# Proiect_TSC_v6.net
KiCad netlist of a schematic drawn in EAGLE
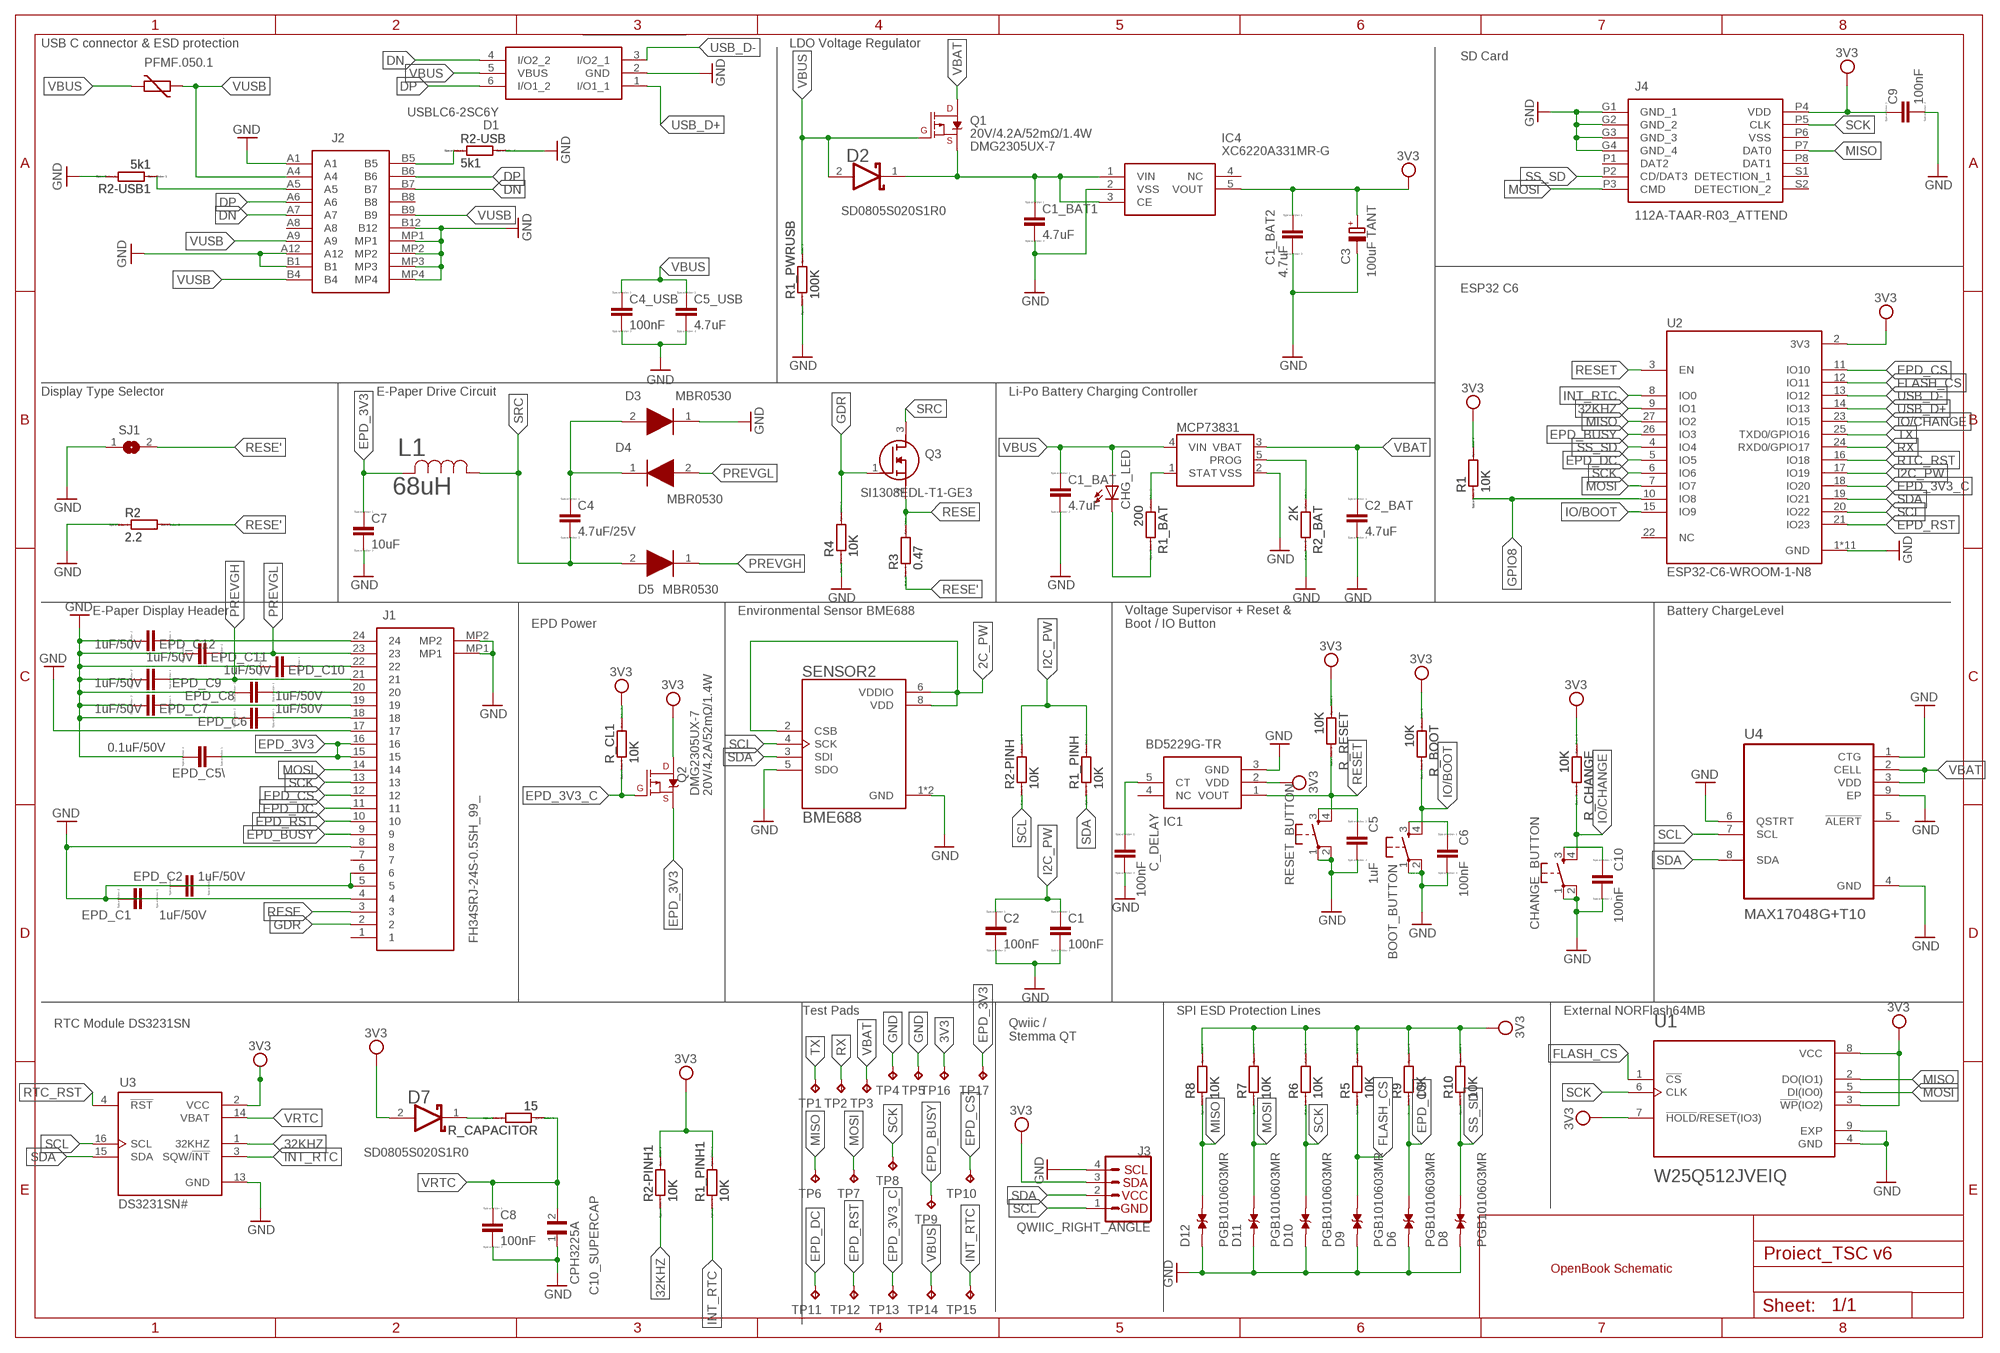
[diagram p0: schematic, sheet 1]

(export (version "E")
  (design (tool "Eeschema 10.0.6"))
  (components
    (comp (ref "BOOT_BUTTON")
      (value "BUTTON_CUSYOMV1")
      (footprint "eagle-import:MYBUTTON")
      (libsource (lib "eagle-import") (part "BUTTON_CUSYOMV1"))
    )
    (comp (ref "C1")
      (value "100nF")
      (footprint "eagle-import:ESP32_WROVER_EAGLE-LTSPICE_C0402")
      (libsource (lib "eagle-import") (part "ESP32_WROVER_EAGLE-LTSPICE_CC0402"))
    )
    (comp (ref "C1_BAT")
      (value "4.7uF")
      (footprint "eagle-import:ESP32_WROVER_EAGLE-LTSPICE_C0402")
      (libsource (lib "eagle-import") (part "ESP32_WROVER_EAGLE-LTSPICE_CC0402"))
    )
    (comp (ref "C1_BAT1")
      (value "4.7uF")
      (footprint "eagle-import:ESP32_WROVER_EAGLE-LTSPICE_C0402")
      (libsource (lib "eagle-import") (part "ESP32_WROVER_EAGLE-LTSPICE_CC0402"))
    )
    (comp (ref "C1_BAT2")
      (value "4.7uF")
      (footprint "eagle-import:ESP32_WROVER_EAGLE-LTSPICE_C0402")
      (libsource (lib "eagle-import") (part "ESP32_WROVER_EAGLE-LTSPICE_CC0402"))
    )
    (comp (ref "C2")
      (value "100nF")
      (footprint "eagle-import:ESP32_WROVER_EAGLE-LTSPICE_C0402")
      (libsource (lib "eagle-import") (part "ESP32_WROVER_EAGLE-LTSPICE_CC0402"))
    )
    (comp (ref "C2_BAT")
      (value "4.7uF")
      (footprint "eagle-import:ESP32_WROVER_EAGLE-LTSPICE_C0402")
      (libsource (lib "eagle-import") (part "ESP32_WROVER_EAGLE-LTSPICE_CC0402"))
    )
    (comp (ref "C3")
      (value "100uF TANT")
      (footprint "eagle-import:RCL_CT3528")
      (libsource (lib "eagle-import") (part "RCL_CPOL-EUCT3528"))
    )
    (comp (ref "C4")
      (value "4.7uF/25V")
      (footprint "eagle-import:ESP32_WROVER_EAGLE-LTSPICE_C0402")
      (libsource (lib "eagle-import") (part "ESP32_WROVER_EAGLE-LTSPICE_CC0402"))
    )
    (comp (ref "C4_USB")
      (value "100nF")
      (footprint "eagle-import:ESP32_WROVER_EAGLE-LTSPICE_C0402")
      (libsource (lib "eagle-import") (part "ESP32_WROVER_EAGLE-LTSPICE_CC0402"))
    )
    (comp (ref "C5")
      (value "1uF")
      (footprint "eagle-import:ESP32_WROVER_EAGLE-LTSPICE_C0402")
      (libsource (lib "eagle-import") (part "ESP32_WROVER_EAGLE-LTSPICE_CC0402"))
    )
    (comp (ref "C5_USB")
      (value "4.7uF")
      (footprint "eagle-import:ESP32_WROVER_EAGLE-LTSPICE_C0402")
      (libsource (lib "eagle-import") (part "ESP32_WROVER_EAGLE-LTSPICE_CC0402"))
    )
    (comp (ref "C6")
      (value "100nF")
      (footprint "eagle-import:ESP32_WROVER_EAGLE-LTSPICE_C0402")
      (libsource (lib "eagle-import") (part "ESP32_WROVER_EAGLE-LTSPICE_CC0402"))
    )
    (comp (ref "C7")
      (value "10uF")
      (footprint "eagle-import:ESP32_WROVER_EAGLE-LTSPICE_C0402")
      (libsource (lib "eagle-import") (part "ESP32_WROVER_EAGLE-LTSPICE_CC0402"))
    )
    (comp (ref "C8")
      (value "100nF")
      (footprint "eagle-import:ESP32_WROVER_EAGLE-LTSPICE_C0402")
      (libsource (lib "eagle-import") (part "ESP32_WROVER_EAGLE-LTSPICE_CC0402"))
    )
    (comp (ref "C9")
      (value "100nF")
      (footprint "eagle-import:ESP32_WROVER_EAGLE-LTSPICE_C0402")
      (libsource (lib "eagle-import") (part "ESP32_WROVER_EAGLE-LTSPICE_CC0402"))
    )
    (comp (ref "C10")
      (value "100nF")
      (footprint "eagle-import:ESP32_WROVER_EAGLE-LTSPICE_C0402")
      (libsource (lib "eagle-import") (part "ESP32_WROVER_EAGLE-LTSPICE_CC0402"))
    )
    (comp (ref "C10_SUPERCAP")
      (value "CPH3225A")
      (footprint "eagle-import:CAPCP3225X100N")
      (fields (field (name "MF") "Seiko Instruments"))
      (libsource (lib "eagle-import") (part "CPH3225A"))
    )
    (comp (ref "CHANGE_BUTTON")
      (value "BUTTON_CUSYOMV1")
      (footprint "eagle-import:MYBUTTON")
      (libsource (lib "eagle-import") (part "BUTTON_CUSYOMV1"))
    )
    (comp (ref "CHG_LED")
      (value "ADAFRUIT_LEDCHIP-LED0603")
      (footprint "eagle-import:ADAFRUIT_CHIP-LED0603")
      (libsource (lib "eagle-import") (part "ADAFRUIT_LEDCHIP-LED0603"))
    )
    (comp (ref "C_DELAY")
      (value "100nF")
      (footprint "eagle-import:ESP32_WROVER_EAGLE-LTSPICE_C0402")
      (libsource (lib "eagle-import") (part "ESP32_WROVER_EAGLE-LTSPICE_CC0402"))
    )
    (comp (ref "D1")
      (value "USBLC6-2SC6Y")
      (footprint "eagle-import:SOT95P280X145-6N")
      (fields (field (name "MF") "STMicroelectronics"))
      (libsource (lib "eagle-import") (part "USBLC6-2SC6Y"))
    )
    (comp (ref "D2")
      (value "ESP32_WROVER_AVX---SD0805S020S1R0_AVX_SD0805S020S1R0_0_0AVX_SD0805S020S1R0_0_0")
      (footprint "eagle-import:ESP32_WROVER_AVX---SD0805S020S1R0_AVX_SD0805S020S1R0_0")
      (fields
        (field (name "DIGIKEY_PART_NUMBER") "478-7800-1-ND")
        (field (name "MF") "AVX")
        (field (name "MOUSER_PART_NUMBER") "581-SD0805S020S1R0")
      )
      (libsource (lib "eagle-import") (part "ESP32_WROVER_AVX---SD0805S020S1R0_AVX_SD0805S020S1R0_0_0AVX_SD0805S020S1R0_0_0"))
    )
    (comp (ref "D3")
      (value "MBR0530")
      (footprint "eagle-import:SOD3716X135N")
      (fields (field (name "MF") "ON Semiconductor"))
      (libsource (lib "eagle-import") (part "MBR0530"))
    )
    (comp (ref "D4")
      (value "MBR0530")
      (footprint "eagle-import:SOD3716X135N")
      (fields (field (name "MF") "ON Semiconductor"))
      (libsource (lib "eagle-import") (part "MBR0530"))
    )
    (comp (ref "D5")
      (value "MBR0530")
      (footprint "eagle-import:SOD3716X135N")
      (fields (field (name "MF") "ON Semiconductor"))
      (libsource (lib "eagle-import") (part "MBR0530"))
    )
    (comp (ref "D6")
      (value "PGB1010603MR")
      (footprint "eagle-import:DIOC1608X36N")
      (fields (field (name "MF") "Littelfuse Inc."))
      (libsource (lib "eagle-import") (part "PGB1010603MR"))
    )
    (comp (ref "D7")
      (value "ESP32_WROVER_AVX---SD0805S020S1R0_AVX_SD0805S020S1R0_0_0AVX_SD0805S020S1R0_0_0")
      (footprint "eagle-import:ESP32_WROVER_AVX---SD0805S020S1R0_AVX_SD0805S020S1R0_0")
      (fields
        (field (name "DIGIKEY_PART_NUMBER") "478-7800-1-ND")
        (field (name "MF") "AVX")
        (field (name "MOUSER_PART_NUMBER") "581-SD0805S020S1R0")
      )
      (libsource (lib "eagle-import") (part "ESP32_WROVER_AVX---SD0805S020S1R0_AVX_SD0805S020S1R0_0_0AVX_SD0805S020S1R0_0_0"))
    )
    (comp (ref "D8")
      (value "PGB1010603MR")
      (footprint "eagle-import:DIOC1608X36N")
      (fields (field (name "MF") "Littelfuse Inc."))
      (libsource (lib "eagle-import") (part "PGB1010603MR"))
    )
    (comp (ref "D9")
      (value "PGB1010603MR")
      (footprint "eagle-import:DIOC1608X36N")
      (fields (field (name "MF") "Littelfuse Inc."))
      (libsource (lib "eagle-import") (part "PGB1010603MR"))
    )
    (comp (ref "D10")
      (value "PGB1010603MR")
      (footprint "eagle-import:DIOC1608X36N")
      (fields (field (name "MF") "Littelfuse Inc."))
      (libsource (lib "eagle-import") (part "PGB1010603MR"))
    )
    (comp (ref "D11")
      (value "PGB1010603MR")
      (footprint "eagle-import:DIOC1608X36N")
      (fields (field (name "MF") "Littelfuse Inc."))
      (libsource (lib "eagle-import") (part "PGB1010603MR"))
    )
    (comp (ref "D12")
      (value "PGB1010603MR")
      (footprint "eagle-import:DIOC1608X36N")
      (fields (field (name "MF") "Littelfuse Inc."))
      (libsource (lib "eagle-import") (part "PGB1010603MR"))
    )
    (comp (ref "EPD_C1")
      (value "1uF/50V")
      (footprint "eagle-import:ESP32_WROVER_EAGLE-LTSPICE_C0402")
      (libsource (lib "eagle-import") (part "ESP32_WROVER_EAGLE-LTSPICE_CC0402"))
    )
    (comp (ref "EPD_C2")
      (value "1uF/50V")
      (footprint "eagle-import:ESP32_WROVER_EAGLE-LTSPICE_C0402")
      (libsource (lib "eagle-import") (part "ESP32_WROVER_EAGLE-LTSPICE_CC0402"))
    )
    (comp (ref "EPD_C5\\")
      (value "0.1uF/50V")
      (footprint "eagle-import:EAGLE-LTSPICE_C0402")
      (libsource (lib "eagle-import") (part "EAGLE-LTSPICE_CC0402"))
    )
    (comp (ref "EPD_C6")
      (value "1uF/50V")
      (footprint "eagle-import:EAGLE-LTSPICE_C0402")
      (libsource (lib "eagle-import") (part "EAGLE-LTSPICE_CC0402"))
    )
    (comp (ref "EPD_C7")
      (value "1uF/50V")
      (footprint "eagle-import:EAGLE-LTSPICE_C0402")
      (libsource (lib "eagle-import") (part "EAGLE-LTSPICE_CC0402"))
    )
    (comp (ref "EPD_C8")
      (value "1uF/50V")
      (footprint "eagle-import:EAGLE-LTSPICE_C0402")
      (libsource (lib "eagle-import") (part "EAGLE-LTSPICE_CC0402"))
    )
    (comp (ref "EPD_C9")
      (value "1uF/50V")
      (footprint "eagle-import:EAGLE-LTSPICE_C0402")
      (libsource (lib "eagle-import") (part "EAGLE-LTSPICE_CC0402"))
    )
    (comp (ref "EPD_C10")
      (value "1uF/50V")
      (footprint "eagle-import:EAGLE-LTSPICE_C0402")
      (libsource (lib "eagle-import") (part "EAGLE-LTSPICE_CC0402"))
    )
    (comp (ref "EPD_C11")
      (value "1uF/50V")
      (footprint "eagle-import:EAGLE-LTSPICE_C0402")
      (libsource (lib "eagle-import") (part "EAGLE-LTSPICE_CC0402"))
    )
    (comp (ref "EPD_C12")
      (value "1uF/50V")
      (footprint "eagle-import:EAGLE-LTSPICE_C0402")
      (libsource (lib "eagle-import") (part "EAGLE-LTSPICE_CC0402"))
    )
    (comp (ref "IC1")
      (value "BD5229G-TR")
      (footprint "eagle-import:SOT95P280X125-5N")
      (fields (field (name "MOUSER_PART_NUMBER") "755-BD5229G-TR"))
      (libsource (lib "eagle-import") (part "BD5229G-TR"))
    )
    (comp (ref "IC4")
      (value "XC6220A331MR-G")
      (footprint "eagle-import:SOT95P280X120-5N")
      (fields (field (name "MOUSER_PART_NUMBER") "865-XC6220A331MR-G"))
      (libsource (lib "eagle-import") (part "XC6220A331MR-G"))
    )
    (comp (ref "J1")
      (value "FH34SRJ-24S-0.5SH_99_")
      (footprint "eagle-import:FH34SRJ24S05SH99")
      (fields
        (field (name "MANUFACTURER_PART_NUMBER") "FH34SRJ-24S-0.5SH(99)")
        (field (name "MOUSER_PART_NUMBER") "798-FH34SRJ24S05SH99")
      )
      (libsource (lib "eagle-import") (part "FH34SRJ-24S-0.5SH_99_"))
    )
    (comp (ref "J2")
      (value "SAMACSYS_PARTS_USB4110-GF-A")
      (footprint "eagle-import:SAMACSYS_PARTS_USB4110GFA")
      (fields
        (field (name "MANUFACTURER_PART_NUMBER") "USB4110-GF-A")
        (field (name "MOUSER_PART_NUMBER") "640-USB4110-GF-A")
      )
      (libsource (lib "eagle-import") (part "SAMACSYS_PARTS_USB4110-GF-A"))
    )
    (comp (ref "J3")
      (value "QWIIC_RIGHT_ANGLE")
      (footprint "eagle-import:JST04_1MM_RA")
      (libsource (lib "eagle-import") (part "QWIIC_CONNECTORJS-1MM"))
    )
    (comp (ref "J4")
      (value "112A-TAAR-R03_ATTEND")
      (footprint "eagle-import:112ATAARR03ATTEND")
      (fields (field (name "MANUFACTURER_PART_NUMBER") "112A-TAAR-R03 ATTEND"))
      (libsource (lib "eagle-import") (part "112A-TAAR-R03_ATTEND"))
    )
    (comp (ref "L1")
      (value "68uH")
      (footprint "eagle-import:IND_4828-WE-TPC_WRE")
      (fields
        (field (name "MANUFACTURER_PART_NUMBER") "744043680")
        (field (name "COPYRIGHT") "Copyright (C) 2024 Ultra Librarian. All rights reserved.")
      )
      (libsource (lib "eagle-import") (part "744043680IND_4828-WE-TPC_WRE"))
    )
    (comp (ref "MCP73831")
      (value "ESP32_WROVER_SPARKFUN-IC-POWER_MCP73831")
      (footprint "eagle-import:ESP32_WROVER_SPARKFUN-IC-POWER_SOT23-5")
      (libsource (lib "eagle-import") (part "ESP32_WROVER_SPARKFUN-IC-POWER_MCP73831"))
    )
    (comp (ref "PFMF.050.1")
      (value "ESP32C6_VARISTORCN1812")
      (footprint "eagle-import:ESP32C6_VARISTOR_CT_CN1812")
      (libsource (lib "eagle-import") (part "ESP32C6_VARISTORCN1812"))
    )
    (comp (ref "Q1")
      (value "20V/4.2A/52mΩ/1.4W")
      (footprint "eagle-import:ESP32_WROVER_SPARKFUN-DISCRETESEMI_SOT23-3")
      (libsource (lib "eagle-import") (part "ESP32_WROVER_SPARKFUN-DISCRETESEMI_MOSFET_PCH-DMG2305UX-7"))
    )
    (comp (ref "Q2")
      (value "20V/4.2A/52mΩ/1.4W")
      (footprint "eagle-import:ESP32_WROVER_SPARKFUN-DISCRETESEMI_SOT23-3")
      (libsource (lib "eagle-import") (part "ESP32_WROVER_SPARKFUN-DISCRETESEMI_MOSFET_PCH-DMG2305UX-7"))
    )
    (comp (ref "Q3")
      (value "SI1308EDL-T1-GE3")
      (footprint "eagle-import:SOT65P210X110-3N")
      (fields (field (name "MF") "Vishay Siliconix"))
      (libsource (lib "eagle-import") (part "SI1308EDL-T1-GE3"))
    )
    (comp (ref "R1")
      (value "10K")
      (footprint "eagle-import:ESP32_WROVER_EAGLE-LTSPICE_R0402")
      (libsource (lib "eagle-import") (part "ESP32_WROVER_EAGLE-LTSPICE_RR0402"))
    )
    (comp (ref "R1_BAT")
      (value "200")
      (footprint "eagle-import:ESP32_WROVER_EAGLE-LTSPICE_R0402")
      (libsource (lib "eagle-import") (part "ESP32_WROVER_EAGLE-LTSPICE_RR0402"))
    )
    (comp (ref "R1_PINH")
      (value "10K")
      (footprint "eagle-import:ESP32_WROVER_EAGLE-LTSPICE_R0402")
      (libsource (lib "eagle-import") (part "ESP32_WROVER_EAGLE-LTSPICE_RR0402"))
    )
    (comp (ref "R1_PINH1")
      (value "10K")
      (footprint "eagle-import:ESP32_WROVER_EAGLE-LTSPICE_R0402")
      (libsource (lib "eagle-import") (part "ESP32_WROVER_EAGLE-LTSPICE_RR0402"))
    )
    (comp (ref "R1_PWRUSB")
      (value "100K")
      (footprint "eagle-import:ESP32_WROVER_EAGLE-LTSPICE_R0402")
      (libsource (lib "eagle-import") (part "ESP32_WROVER_EAGLE-LTSPICE_RR0402"))
    )
    (comp (ref "R2")
      (value "2.2")
      (footprint "eagle-import:ESP32_WROVER_EAGLE-LTSPICE_R0402")
      (libsource (lib "eagle-import") (part "ESP32_WROVER_EAGLE-LTSPICE_RR0402"))
    )
    (comp (ref "R2-PINH")
      (value "10K")
      (footprint "eagle-import:ESP32_WROVER_EAGLE-LTSPICE_R0402")
      (libsource (lib "eagle-import") (part "ESP32_WROVER_EAGLE-LTSPICE_RR0402"))
    )
    (comp (ref "R2-PINH1")
      (value "10K")
      (footprint "eagle-import:ESP32_WROVER_EAGLE-LTSPICE_R0402")
      (libsource (lib "eagle-import") (part "ESP32_WROVER_EAGLE-LTSPICE_RR0402"))
    )
    (comp (ref "R2-USB")
      (value "5k1")
      (footprint "eagle-import:ESP32_WROVER_EAGLE-LTSPICE_R0402")
      (libsource (lib "eagle-import") (part "ESP32_WROVER_EAGLE-LTSPICE_RR0402"))
    )
    (comp (ref "R2-USB1")
      (value "5k1")
      (footprint "eagle-import:ESP32_WROVER_EAGLE-LTSPICE_R0402")
      (libsource (lib "eagle-import") (part "ESP32_WROVER_EAGLE-LTSPICE_RR0402"))
    )
    (comp (ref "R2_BAT")
      (value "2K")
      (footprint "eagle-import:ESP32_WROVER_EAGLE-LTSPICE_R0402")
      (libsource (lib "eagle-import") (part "ESP32_WROVER_EAGLE-LTSPICE_RR0402"))
    )
    (comp (ref "R3")
      (value "0.47")
      (footprint "eagle-import:ESP32_WROVER_EAGLE-LTSPICE_R0402")
      (libsource (lib "eagle-import") (part "ESP32_WROVER_EAGLE-LTSPICE_RR0402"))
    )
    (comp (ref "R4")
      (value "10K")
      (footprint "eagle-import:ESP32_WROVER_EAGLE-LTSPICE_R0402")
      (libsource (lib "eagle-import") (part "ESP32_WROVER_EAGLE-LTSPICE_RR0402"))
    )
    (comp (ref "R5")
      (value "10K")
      (footprint "eagle-import:ESP32_WROVER_EAGLE-LTSPICE_R0402")
      (libsource (lib "eagle-import") (part "ESP32_WROVER_EAGLE-LTSPICE_RR0402"))
    )
    (comp (ref "R6")
      (value "10K")
      (footprint "eagle-import:ESP32_WROVER_EAGLE-LTSPICE_R0402")
      (libsource (lib "eagle-import") (part "ESP32_WROVER_EAGLE-LTSPICE_RR0402"))
    )
    (comp (ref "R7")
      (value "10K")
      (footprint "eagle-import:ESP32_WROVER_EAGLE-LTSPICE_R0402")
      (libsource (lib "eagle-import") (part "ESP32_WROVER_EAGLE-LTSPICE_RR0402"))
    )
    (comp (ref "R8")
      (value "10K")
      (footprint "eagle-import:ESP32_WROVER_EAGLE-LTSPICE_R0402")
      (libsource (lib "eagle-import") (part "ESP32_WROVER_EAGLE-LTSPICE_RR0402"))
    )
    (comp (ref "R9")
      (value "10K")
      (footprint "eagle-import:ESP32_WROVER_EAGLE-LTSPICE_R0402")
      (libsource (lib "eagle-import") (part "ESP32_WROVER_EAGLE-LTSPICE_RR0402"))
    )
    (comp (ref "R10")
      (value "10K")
      (footprint "eagle-import:ESP32_WROVER_EAGLE-LTSPICE_R0402")
      (libsource (lib "eagle-import") (part "ESP32_WROVER_EAGLE-LTSPICE_RR0402"))
    )
    (comp (ref "RESET_BUTTON")
      (value "BUTTON_CUSYOMV1")
      (footprint "eagle-import:MYBUTTON")
      (libsource (lib "eagle-import") (part "BUTTON_CUSYOMV1"))
    )
    (comp (ref "R_BOOT")
      (value "10K")
      (footprint "eagle-import:ESP32_WROVER_EAGLE-LTSPICE_R0402")
      (libsource (lib "eagle-import") (part "ESP32_WROVER_EAGLE-LTSPICE_RR0402"))
    )
    (comp (ref "R_CAPACITOR")
      (value "15")
      (footprint "eagle-import:ESP32_WROVER_EAGLE-LTSPICE_R0402")
      (libsource (lib "eagle-import") (part "ESP32_WROVER_EAGLE-LTSPICE_RR0402"))
    )
    (comp (ref "R_CHANGE")
      (value "10K")
      (footprint "eagle-import:ESP32_WROVER_EAGLE-LTSPICE_R0402")
      (libsource (lib "eagle-import") (part "ESP32_WROVER_EAGLE-LTSPICE_RR0402"))
    )
    (comp (ref "R_CL1")
      (value "10K")
      (footprint "eagle-import:ESP32_WROVER_EAGLE-LTSPICE_R0402")
      (libsource (lib "eagle-import") (part "ESP32_WROVER_EAGLE-LTSPICE_RR0402"))
    )
    (comp (ref "R_RESET")
      (value "10K")
      (footprint "eagle-import:ESP32_WROVER_EAGLE-LTSPICE_R0402")
      (libsource (lib "eagle-import") (part "ESP32_WROVER_EAGLE-LTSPICE_RR0402"))
    )
    (comp (ref "SENSOR2")
      (value "BME688")
      (footprint "eagle-import:ESP32_WROVER_BME680_PSON80P300X300X100-8N")
      (fields (field (name "MF") "Bosch Sensortec") (field (name "MP") "BME680"))
      (libsource (lib "eagle-import") (part "ESP32_WROVER_BME680_BME680"))
    )
    (comp (ref "SJ1") (value "SJ") (footprint "eagle-import:SJ") (libsource (lib "eagle-import") (part "SJ")))
    (comp (ref "TP1")
      (value "TPTP20R")
      (footprint "eagle-import:TP20R")
      (libsource (lib "eagle-import") (part "TPTP20R"))
    )
    (comp (ref "TP2")
      (value "TPTP20R")
      (footprint "eagle-import:TP20R")
      (libsource (lib "eagle-import") (part "TPTP20R"))
    )
    (comp (ref "TP3")
      (value "TPTP20R")
      (footprint "eagle-import:TP20R")
      (libsource (lib "eagle-import") (part "TPTP20R"))
    )
    (comp (ref "TP4")
      (value "TPTP20R")
      (footprint "eagle-import:TP20R")
      (libsource (lib "eagle-import") (part "TPTP20R"))
    )
    (comp (ref "TP5")
      (value "TPTP20R")
      (footprint "eagle-import:TP20R")
      (libsource (lib "eagle-import") (part "TPTP20R"))
    )
    (comp (ref "TP6")
      (value "TPTP20R")
      (footprint "eagle-import:TP20R")
      (libsource (lib "eagle-import") (part "TPTP20R"))
    )
    (comp (ref "TP7")
      (value "TPTP20R")
      (footprint "eagle-import:TP20R")
      (libsource (lib "eagle-import") (part "TPTP20R"))
    )
    (comp (ref "TP8")
      (value "TPTP20R")
      (footprint "eagle-import:TP20R")
      (libsource (lib "eagle-import") (part "TPTP20R"))
    )
    (comp (ref "TP9")
      (value "TPTP20R")
      (footprint "eagle-import:TP20R")
      (libsource (lib "eagle-import") (part "TPTP20R"))
    )
    (comp (ref "TP10")
      (value "TPTP20R")
      (footprint "eagle-import:TP20R")
      (libsource (lib "eagle-import") (part "TPTP20R"))
    )
    (comp (ref "TP11")
      (value "TPTP20R")
      (footprint "eagle-import:TP20R")
      (libsource (lib "eagle-import") (part "TPTP20R"))
    )
    (comp (ref "TP12")
      (value "TPTP20R")
      (footprint "eagle-import:TP20R")
      (libsource (lib "eagle-import") (part "TPTP20R"))
    )
    (comp (ref "TP13")
      (value "TPTP20R")
      (footprint "eagle-import:TP20R")
      (libsource (lib "eagle-import") (part "TPTP20R"))
    )
    (comp (ref "TP14")
      (value "TPTP20R")
      (footprint "eagle-import:TP20R")
      (libsource (lib "eagle-import") (part "TPTP20R"))
    )
    (comp (ref "TP15")
      (value "TPTP20R")
      (footprint "eagle-import:TP20R")
      (libsource (lib "eagle-import") (part "TPTP20R"))
    )
    (comp (ref "TP16")
      (value "TPTP20R")
      (footprint "eagle-import:TP20R")
      (libsource (lib "eagle-import") (part "TPTP20R"))
    )
    (comp (ref "TP17")
      (value "TPTP20R")
      (footprint "eagle-import:TP20R")
      (libsource (lib "eagle-import") (part "TPTP20R"))
    )
    (comp (ref "U1")
      (value "W25Q512JVEIQ")
      (footprint "eagle-import:SON127P600X800X80-9N")
      (fields (field (name "MF") "Winbond Electronics"))
      (libsource (lib "eagle-import") (part "W25Q512JVEIQ"))
    )
    (comp (ref "U2")
      (value "ESP32-C6-WROOM-1-N8")
      (footprint "eagle-import:XCVR_ESP32-C6-WROOM-1-N8")
      (fields (field (name "MF") "Espressif Systems"))
      (libsource (lib "eagle-import") (part "ESP32-C6-WROOM-1-N8"))
    )
    (comp (ref "U3")
      (value "DS3231SN#")
      (footprint "eagle-import:SOIC127P1032X265-16N")
      (fields (field (name "MF") "Analog Devices"))
      (libsource (lib "eagle-import") (part "DS3231SN#"))
    )
    (comp (ref "U4")
      (value "MAX17048G+T10")
      (footprint "eagle-import:SON50P200X200X80-9N")
      (fields (field (name "MF") "Analog Devices"))
      (libsource (lib "eagle-import") (part "MAX17048G+T10"))
    )
  )
  (nets
    (net (code "1") (name "2C_PW") (class "Default")
      (node (ref "SENSOR2") (pin "2") (pinfunction "CSB_2") (pintype "input"))
      (node (ref "SENSOR2") (pin "6") (pinfunction "VDDIO_6") (pintype "power_in"))
      (node (ref "SENSOR2") (pin "8") (pinfunction "VDD_8") (pintype "power_in"))
    )
    (net (code "2") (name "3V3") (class "Default")
      (node (ref "C1_BAT2") (pin "1") (pinfunction "1_1") (pintype "passive"))
      (node (ref "C3") (pin "+") (pinfunction "+_+") (pintype "passive"))
      (node (ref "C9") (pin "1") (pinfunction "1_1") (pintype "passive"))
      (node (ref "D7") (pin "2") (pinfunction "ANODE_2") (pintype "bidirectional"))
      (node (ref "IC1") (pin "2") (pinfunction "VDD_2") (pintype "bidirectional"))
      (node (ref "IC4") (pin "5") (pinfunction "VOUT_5") (pintype "bidirectional"))
      (node (ref "J3") (pin "3") (pinfunction "3_3") (pintype "passive"))
      (node (ref "J4") (pin "P4") (pinfunction "VDD_P4") (pintype "bidirectional"))
      (node (ref "Q2") (pin "3") (pinfunction "D_3") (pintype "bidirectional"))
      (node (ref "R1") (pin "2") (pinfunction "2_2") (pintype "passive"))
      (node (ref "R10") (pin "2") (pinfunction "2_2") (pintype "passive"))
      (node (ref "R1_PINH1") (pin "2") (pinfunction "2_2") (pintype "passive"))
      (node (ref "R2-PINH1") (pin "2") (pinfunction "2_2") (pintype "passive"))
      (node (ref "R5") (pin "2") (pinfunction "2_2") (pintype "passive"))
      (node (ref "R6") (pin "2") (pinfunction "2_2") (pintype "passive"))
      (node (ref "R7") (pin "2") (pinfunction "2_2") (pintype "passive"))
      (node (ref "R8") (pin "2") (pinfunction "2_2") (pintype "passive"))
      (node (ref "R9") (pin "2") (pinfunction "2_2") (pintype "passive"))
      (node (ref "R_BOOT") (pin "1") (pinfunction "1_1") (pintype "passive"))
      (node (ref "R_CHANGE") (pin "1") (pinfunction "1_1") (pintype "passive"))
      (node (ref "R_CL1") (pin "2") (pinfunction "2_2") (pintype "passive"))
      (node (ref "R_RESET") (pin "1") (pinfunction "1_1") (pintype "passive"))
      (node (ref "TP16") (pin "TP") (pinfunction "TP_TP") (pintype "input"))
      (node (ref "U1") (pin "3") (pinfunction "~{WP}(IO2)_3") (pintype "bidirectional"))
      (node (ref "U1") (pin "7") (pinfunction "~{HOLD}/~{RESET}(IO3)_7") (pintype "bidirectional"))
      (node (ref "U1") (pin "8") (pinfunction "VCC_8") (pintype "power_in"))
      (node (ref "U2") (pin "2") (pinfunction "3V3_2") (pintype "power_in"))
      (node (ref "U3") (pin "2") (pinfunction "VCC_2") (pintype "power_in"))
    )
    (net (code "3") (name "32KHZ") (class "Default")
      (node (ref "R2-PINH1") (pin "1") (pinfunction "1_1") (pintype "passive"))
      (node (ref "U2") (pin "9") (pinfunction "IO1_9") (pintype "bidirectional"))
      (node (ref "U3") (pin "1") (pinfunction "32KHZ_1") (pintype "output"))
    )
    (net (code "4") (name "DN") (class "Default")
      (node (ref "D1") (pin "4") (pinfunction "I/O2_2_4") (pintype "bidirectional"))
      (node (ref "J2") (pin "A7") (pinfunction "A7_A7") (pintype "bidirectional"))
      (node (ref "J2") (pin "B7") (pinfunction "B7_B7") (pintype "bidirectional"))
    )
    (net (code "5") (name "DP") (class "Default")
      (node (ref "D1") (pin "6") (pinfunction "I/O1_2_6") (pintype "bidirectional"))
      (node (ref "J2") (pin "A6") (pinfunction "A6_A6") (pintype "bidirectional"))
      (node (ref "J2") (pin "B6") (pinfunction "B6_B6") (pintype "bidirectional"))
    )
    (net (code "6") (name "EPD_3V3") (class "Default")
      (node (ref "C7") (pin "1") (pinfunction "1_1") (pintype "passive"))
      (node (ref "EPD_C5\\") (pin "1") (pinfunction "1_1") (pintype "passive"))
      (node (ref "J1") (pin "15") (pinfunction "15_15") (pintype "bidirectional"))
      (node (ref "J1") (pin "16") (pinfunction "16_16") (pintype "bidirectional"))
      (node (ref "L1") (pin "2") (pinfunction "2_2") (pintype "passive"))
      (node (ref "Q2") (pin "2") (pinfunction "S_2") (pintype "bidirectional"))
      (node (ref "TP17") (pin "TP") (pinfunction "TP_TP") (pintype "input"))
    )
    (net (code "7") (name "EPD_3V3_C") (class "Default")
      (node (ref "Q2") (pin "1") (pinfunction "G_1") (pintype "bidirectional"))
      (node (ref "R_CL1") (pin "1") (pinfunction "1_1") (pintype "passive"))
      (node (ref "TP13") (pin "TP") (pinfunction "TP_TP") (pintype "input"))
      (node (ref "U2") (pin "18") (pinfunction "IO20_18") (pintype "bidirectional"))
    )
    (net (code "8") (name "EPD_BUSY") (class "Default")
      (node (ref "J1") (pin "9") (pinfunction "9_9") (pintype "bidirectional"))
      (node (ref "TP9") (pin "TP") (pinfunction "TP_TP") (pintype "input"))
      (node (ref "U2") (pin "26") (pinfunction "IO3_26") (pintype "bidirectional"))
    )
    (net (code "9") (name "EPD_CS") (class "Default")
      (node (ref "D6") (pin "2") (pinfunction "2_2") (pintype "passive"))
      (node (ref "J1") (pin "12") (pinfunction "12_12") (pintype "bidirectional"))
      (node (ref "R9") (pin "1") (pinfunction "1_1") (pintype "passive"))
      (node (ref "TP10") (pin "TP") (pinfunction "TP_TP") (pintype "input"))
      (node (ref "U2") (pin "11") (pinfunction "IO10_11") (pintype "bidirectional"))
    )
    (net (code "10") (name "EPD_DC") (class "Default")
      (node (ref "J1") (pin "11") (pinfunction "11_11") (pintype "bidirectional"))
      (node (ref "TP11") (pin "TP") (pinfunction "TP_TP") (pintype "input"))
      (node (ref "U2") (pin "5") (pinfunction "IO5_5") (pintype "bidirectional"))
    )
    (net (code "11") (name "EPD_RST") (class "Default")
      (node (ref "J1") (pin "10") (pinfunction "10_10") (pintype "bidirectional"))
      (node (ref "TP12") (pin "TP") (pinfunction "TP_TP") (pintype "input"))
      (node (ref "U2") (pin "21") (pinfunction "IO23_21") (pintype "bidirectional"))
    )
    (net (code "12") (name "FLASH_CS") (class "Default")
      (node (ref "D9") (pin "2") (pinfunction "2_2") (pintype "passive"))
      (node (ref "R5") (pin "1") (pinfunction "1_1") (pintype "passive"))
      (node (ref "U1") (pin "1") (pinfunction "~{CS}_1") (pintype "input"))
      (node (ref "U2") (pin "12") (pinfunction "IO11_12") (pintype "bidirectional"))
    )
    (net (code "13") (name "GDR") (class "Default")
      (node (ref "J1") (pin "2") (pinfunction "2_2") (pintype "bidirectional"))
      (node (ref "Q3") (pin "1") (pinfunction "G_1") (pintype "bidirectional"))
      (node (ref "R4") (pin "2") (pinfunction "2_2") (pintype "passive"))
    )
    (net (code "14") (name "GND") (class "Default")
      (node (ref "BOOT_BUTTON") (pin "2") (pinfunction "2_2") (pintype "passive"))
      (node (ref "C1") (pin "2") (pinfunction "2_2") (pintype "passive"))
      (node (ref "C10") (pin "2") (pinfunction "2_2") (pintype "passive"))
      (node (ref "C10_SUPERCAP") (pin "1") (pinfunction "1_1") (pintype "passive"))
      (node (ref "C1_BAT") (pin "2") (pinfunction "2_2") (pintype "passive"))
      (node (ref "C1_BAT1") (pin "2") (pinfunction "2_2") (pintype "passive"))
      (node (ref "C1_BAT2") (pin "2") (pinfunction "2_2") (pintype "passive"))
      (node (ref "C2") (pin "2") (pinfunction "2_2") (pintype "passive"))
      (node (ref "C2_BAT") (pin "2") (pinfunction "2_2") (pintype "passive"))
      (node (ref "C3") (pin "-") (pinfunction "-_-") (pintype "passive"))
      (node (ref "C4_USB") (pin "2") (pinfunction "2_2") (pintype "passive"))
      (node (ref "C5") (pin "2") (pinfunction "2_2") (pintype "passive"))
      (node (ref "C5_USB") (pin "2") (pinfunction "2_2") (pintype "passive"))
      (node (ref "C6") (pin "2") (pinfunction "2_2") (pintype "passive"))
      (node (ref "C7") (pin "2") (pinfunction "2_2") (pintype "passive"))
      (node (ref "C8") (pin "2") (pinfunction "2_2") (pintype "passive"))
      (node (ref "C9") (pin "2") (pinfunction "2_2") (pintype "passive"))
      (node (ref "CHANGE_BUTTON") (pin "2") (pinfunction "2_2") (pintype "passive"))
      (node (ref "C_DELAY") (pin "2") (pinfunction "2_2") (pintype "passive"))
      (node (ref "D1") (pin "2") (pinfunction "GND_2") (pintype "bidirectional"))
      (node (ref "D10") (pin "1") (pinfunction "1_1") (pintype "passive"))
      (node (ref "D11") (pin "1") (pinfunction "1_1") (pintype "passive"))
      (node (ref "D12") (pin "1") (pinfunction "1_1") (pintype "passive"))
      (node (ref "D3") (pin "1") (pinfunction "K_1") (pintype "bidirectional"))
      (node (ref "D6") (pin "1") (pinfunction "1_1") (pintype "passive"))
      (node (ref "D8") (pin "1") (pinfunction "1_1") (pintype "passive"))
      (node (ref "D9") (pin "1") (pinfunction "1_1") (pintype "passive"))
      (node (ref "EPD_C1") (pin "1") (pinfunction "1_1") (pintype "passive"))
      (node (ref "EPD_C10") (pin "2") (pinfunction "2_2") (pintype "passive"))
      (node (ref "EPD_C11") (pin "2") (pinfunction "2_2") (pintype "passive"))
      (node (ref "EPD_C12") (pin "2") (pinfunction "2_2") (pintype "passive"))
      (node (ref "EPD_C2") (pin "1") (pinfunction "1_1") (pintype "passive"))
      (node (ref "EPD_C5\\") (pin "2") (pinfunction "2_2") (pintype "passive"))
      (node (ref "EPD_C6") (pin "2") (pinfunction "2_2") (pintype "passive"))
      (node (ref "EPD_C7") (pin "2") (pinfunction "2_2") (pintype "passive"))
      (node (ref "EPD_C8") (pin "2") (pinfunction "2_2") (pintype "passive"))
      (node (ref "EPD_C9") (pin "2") (pinfunction "2_2") (pintype "passive"))
      (node (ref "IC1") (pin "3") (pinfunction "GND_3") (pintype "bidirectional"))
      (node (ref "IC4") (pin "2") (pinfunction "VSS_2") (pintype "bidirectional"))
      (node (ref "J1") (pin "17") (pinfunction "17_17") (pintype "bidirectional"))
      (node (ref "J1") (pin "8") (pinfunction "8_8") (pintype "bidirectional"))
      (node (ref "J1") (pin "MP1") (pinfunction "MP1_MP1") (pintype "bidirectional"))
      (node (ref "J1") (pin "MP2") (pinfunction "MP2_MP2") (pintype "bidirectional"))
      (node (ref "J2") (pin "A1") (pinfunction "A1_A1") (pintype "bidirectional"))
      (node (ref "J2") (pin "A12") (pinfunction "A12_A12") (pintype "bidirectional"))
      (node (ref "J2") (pin "B1") (pinfunction "B1_B1") (pintype "bidirectional"))
      (node (ref "J2") (pin "B12") (pinfunction "B12_B12") (pintype "bidirectional"))
      (node (ref "J2") (pin "MP1") (pinfunction "MP1_MP1") (pintype "bidirectional"))
      (node (ref "J2") (pin "MP2") (pinfunction "MP2_MP2") (pintype "bidirectional"))
      (node (ref "J2") (pin "MP3") (pinfunction "MP3_MP3") (pintype "bidirectional"))
      (node (ref "J2") (pin "MP4") (pinfunction "MP4_MP4") (pintype "bidirectional"))
      (node (ref "J3") (pin "4") (pinfunction "4_4") (pintype "passive"))
      (node (ref "J4") (pin "G1") (pinfunction "GND_1_G1") (pintype "bidirectional"))
      (node (ref "J4") (pin "G2") (pinfunction "GND_2_G2") (pintype "bidirectional"))
      (node (ref "J4") (pin "G3") (pinfunction "GND_3_G3") (pintype "bidirectional"))
      (node (ref "J4") (pin "G4") (pinfunction "GND_4_G4") (pintype "bidirectional"))
      (node (ref "MCP73831") (pin "2") (pinfunction "VSS_2") (pintype "power_in"))
      (node (ref "R1_PWRUSB") (pin "1") (pinfunction "1_1") (pintype "passive"))
      (node (ref "R2") (pin "1") (pinfunction "1_1") (pintype "passive"))
      (node (ref "R2-USB") (pin "2") (pinfunction "2_2") (pintype "passive"))
      (node (ref "R2-USB1") (pin "2") (pinfunction "2_2") (pintype "passive"))
      (node (ref "R2_BAT") (pin "2") (pinfunction "2_2") (pintype "passive"))
      (node (ref "R4") (pin "1") (pinfunction "1_1") (pintype "passive"))
      (node (ref "RESET_BUTTON") (pin "1") (pinfunction "1_1") (pintype "passive"))
      (node (ref "RESET_BUTTON") (pin "2") (pinfunction "2_2") (pintype "passive"))
      (node (ref "SENSOR2") (pin "1") (pinfunction "GND_1") (pintype "power_in"))
      (node (ref "SENSOR2") (pin "5") (pinfunction "SDO_5") (pintype "bidirectional"))
      (node (ref "SENSOR2") (pin "7") (pinfunction "GND_7") (pintype "power_in"))
      (node (ref "SJ1") (pin "1") (pinfunction "1_1") (pintype "passive"))
      (node (ref "TP4") (pin "TP") (pinfunction "TP_TP") (pintype "input"))
      (node (ref "TP5") (pin "TP") (pinfunction "TP_TP") (pintype "input"))
      (node (ref "U1") (pin "4") (pinfunction "GND_4") (pintype "power_in"))
      (node (ref "U1") (pin "9") (pinfunction "EXP_9") (pintype "passive"))
      (node (ref "U2") (pin "1") (pinfunction "GND_1") (pintype "power_in"))
      (node (ref "U2") (pin "28") (pinfunction "GND_28") (pintype "power_in"))
      (node (ref "U2") (pin "29_1") (pinfunction "GND_29_1") (pintype "power_in"))
      (node (ref "U2") (pin "29_2") (pinfunction "GND_29_2") (pintype "power_in"))
      (node (ref "U2") (pin "29_3") (pinfunction "GND_29_3") (pintype "power_in"))
      (node (ref "U2") (pin "29_4") (pinfunction "GND_29_4") (pintype "power_in"))
      (node (ref "U2") (pin "29_5") (pinfunction "GND_29_5") (pintype "power_in"))
      (node (ref "U2") (pin "29_6") (pinfunction "GND_29_6") (pintype "power_in"))
      (node (ref "U2") (pin "29_7") (pinfunction "GND_29_7") (pintype "power_in"))
      (node (ref "U2") (pin "29_8") (pinfunction "GND_29_8") (pintype "power_in"))
      (node (ref "U2") (pin "29_9") (pinfunction "GND_29_9") (pintype "power_in"))
      (node (ref "U3") (pin "13") (pinfunction "GND_13") (pintype "power_in"))
      (node (ref "U4") (pin "1") (pinfunction "CTG_1") (pintype "power_in"))
      (node (ref "U4") (pin "4") (pinfunction "GND_4") (pintype "power_in"))
      (node (ref "U4") (pin "6") (pinfunction "QSTRT_6") (pintype "input"))
      (node (ref "U4") (pin "9") (pinfunction "EP_9") (pintype "power_in"))
    )
    (net (code "15") (name "GPIO8") (class "Default")
      (node (ref "R1") (pin "1") (pinfunction "1_1") (pintype "passive"))
      (node (ref "U2") (pin "10") (pinfunction "IO8_10") (pintype "bidirectional"))
    )
    (net (code "16") (name "I2C_PW") (class "Default")
      (node (ref "C1") (pin "1") (pinfunction "1_1") (pintype "passive"))
      (node (ref "C2") (pin "1") (pinfunction "1_1") (pintype "passive"))
      (node (ref "R1_PINH") (pin "2") (pinfunction "2_2") (pintype "passive"))
      (node (ref "R2-PINH") (pin "2") (pinfunction "2_2") (pintype "passive"))
      (node (ref "U2") (pin "17") (pinfunction "IO19_17") (pintype "bidirectional"))
    )
    (net (code "17") (name "INT_RTC") (class "Default")
      (node (ref "R1_PINH1") (pin "1") (pinfunction "1_1") (pintype "passive"))
      (node (ref "TP15") (pin "TP") (pinfunction "TP_TP") (pintype "input"))
      (node (ref "U2") (pin "8") (pinfunction "IO0_8") (pintype "bidirectional"))
      (node (ref "U3") (pin "3") (pinfunction "SQW/~{INT}_3") (pintype "output"))
    )
    (net (code "18") (name "IO{slash}BOOT") (class "Default")
      (node (ref "BOOT_BUTTON") (pin "4") (pinfunction "4_4") (pintype "passive"))
      (node (ref "R_BOOT") (pin "2") (pinfunction "2_2") (pintype "passive"))
      (node (ref "U2") (pin "15") (pinfunction "IO9_15") (pintype "bidirectional"))
    )
    (net (code "19") (name "IO{slash}CHANGE") (class "Default")
      (node (ref "CHANGE_BUTTON") (pin "4") (pinfunction "4_4") (pintype "passive"))
      (node (ref "R_CHANGE") (pin "2") (pinfunction "2_2") (pintype "passive"))
      (node (ref "U2") (pin "23") (pinfunction "IO15_23") (pintype "bidirectional"))
    )
    (net (code "20") (name "MISO") (class "Default")
      (node (ref "D12") (pin "2") (pinfunction "2_2") (pintype "passive"))
      (node (ref "J4") (pin "P7") (pinfunction "DAT0_P7") (pintype "bidirectional"))
      (node (ref "R8") (pin "1") (pinfunction "1_1") (pintype "passive"))
      (node (ref "TP6") (pin "TP") (pinfunction "TP_TP") (pintype "input"))
      (node (ref "U1") (pin "2") (pinfunction "DO(IO1)_2") (pintype "bidirectional"))
      (node (ref "U2") (pin "27") (pinfunction "IO2_27") (pintype "bidirectional"))
    )
    (net (code "21") (name "MOSI") (class "Default")
      (node (ref "D11") (pin "2") (pinfunction "2_2") (pintype "passive"))
      (node (ref "J1") (pin "14") (pinfunction "14_14") (pintype "bidirectional"))
      (node (ref "J4") (pin "P3") (pinfunction "CMD_P3") (pintype "bidirectional"))
      (node (ref "R7") (pin "1") (pinfunction "1_1") (pintype "passive"))
      (node (ref "TP7") (pin "TP") (pinfunction "TP_TP") (pintype "input"))
      (node (ref "U1") (pin "5") (pinfunction "DI(IO0)_5") (pintype "bidirectional"))
      (node (ref "U2") (pin "7") (pinfunction "IO7_7") (pintype "bidirectional"))
    )
    (net (code "22") (name "Net-(BOOT_BUTTON-Pad3)") (class "Default")
      (node (ref "BOOT_BUTTON") (pin "3") (pinfunction "3_3") (pintype "passive"))
      (node (ref "C6") (pin "1") (pinfunction "1_1") (pintype "passive"))
    )
    (net (code "23") (name "Net-(C5-Pad1)") (class "Default")
      (node (ref "C5") (pin "1") (pinfunction "1_1") (pintype "passive"))
      (node (ref "RESET_BUTTON") (pin "3") (pinfunction "3_3") (pintype "passive"))
    )
    (net (code "24") (name "Net-(C10-Pad1)") (class "Default")
      (node (ref "C10") (pin "1") (pinfunction "1_1") (pintype "passive"))
      (node (ref "CHANGE_BUTTON") (pin "3") (pinfunction "3_3") (pintype "passive"))
    )
    (net (code "25") (name "Net-(CHG_LED-PadC)") (class "Default")
      (node (ref "CHG_LED") (pin "C") (pinfunction "C_C") (pintype "passive"))
      (node (ref "R1_BAT") (pin "2") (pinfunction "2_2") (pintype "passive"))
    )
    (net (code "26") (name "Net-(D2-CATHODE)") (class "Default")
      (node (ref "C1_BAT1") (pin "1") (pinfunction "1_1") (pintype "passive"))
      (node (ref "D2") (pin "1") (pinfunction "CATHODE_1") (pintype "bidirectional"))
      (node (ref "IC4") (pin "1") (pinfunction "VIN_1") (pintype "bidirectional"))
      (node (ref "IC4") (pin "3") (pinfunction "CE_3") (pintype "bidirectional"))
      (node (ref "Q1") (pin "2") (pinfunction "S_2") (pintype "bidirectional"))
    )
    (net (code "27") (name "Net-(D3-A)") (class "Default")
      (node (ref "C4") (pin "1") (pinfunction "1_1") (pintype "passive"))
      (node (ref "D3") (pin "2") (pinfunction "A_2") (pintype "bidirectional"))
      (node (ref "D4") (pin "1") (pinfunction "K_1") (pintype "bidirectional"))
    )
    (net (code "28") (name "Net-(D7-CATHODE)") (class "Default")
      (node (ref "D7") (pin "1") (pinfunction "CATHODE_1") (pintype "bidirectional"))
      (node (ref "R_CAPACITOR") (pin "2") (pinfunction "2_2") (pintype "passive"))
    )
    (net (code "29") (name "Net-(EPD_C1-Pad2)") (class "Default")
      (node (ref "EPD_C1") (pin "2") (pinfunction "2_2") (pintype "passive"))
      (node (ref "J1") (pin "4") (pinfunction "4_4") (pintype "bidirectional"))
    )
    (net (code "30") (name "Net-(EPD_C2-Pad2)") (class "Default")
      (node (ref "EPD_C2") (pin "2") (pinfunction "2_2") (pintype "passive"))
      (node (ref "J1") (pin "5") (pinfunction "5_5") (pintype "bidirectional"))
      (node (ref "J1") (pin "6") (pinfunction "6_6") (pintype "bidirectional"))
    )
    (net (code "31") (name "Net-(EPD_C6-Pad1)") (class "Default")
      (node (ref "EPD_C6") (pin "1") (pinfunction "1_1") (pintype "passive"))
      (node (ref "J1") (pin "18") (pinfunction "18_18") (pintype "bidirectional"))
    )
    (net (code "32") (name "Net-(EPD_C7-Pad1)") (class "Default")
      (node (ref "EPD_C7") (pin "1") (pinfunction "1_1") (pintype "passive"))
      (node (ref "J1") (pin "19") (pinfunction "19_19") (pintype "bidirectional"))
    )
    (net (code "33") (name "Net-(EPD_C8-Pad1)") (class "Default")
      (node (ref "EPD_C8") (pin "1") (pinfunction "1_1") (pintype "passive"))
      (node (ref "J1") (pin "20") (pinfunction "20_20") (pintype "bidirectional"))
    )
    (net (code "34") (name "Net-(EPD_C10-Pad1)") (class "Default")
      (node (ref "EPD_C10") (pin "1") (pinfunction "1_1") (pintype "passive"))
      (node (ref "J1") (pin "22") (pinfunction "22_22") (pintype "bidirectional"))
    )
    (net (code "35") (name "Net-(EPD_C12-Pad1)") (class "Default")
      (node (ref "EPD_C12") (pin "1") (pinfunction "1_1") (pintype "passive"))
      (node (ref "J1") (pin "24") (pinfunction "24_24") (pintype "bidirectional"))
    )
    (net (code "36") (name "Net-(IC1-CT)") (class "Default")
      (node (ref "C_DELAY") (pin "1") (pinfunction "1_1") (pintype "passive"))
      (node (ref "IC1") (pin "5") (pinfunction "CT_5") (pintype "bidirectional"))
    )
    (net (code "37") (name "Net-(J2-PadA5)") (class "Default")
      (node (ref "J2") (pin "A5") (pinfunction "A5_A5") (pintype "bidirectional"))
      (node (ref "R2-USB1") (pin "1") (pinfunction "1_1") (pintype "passive"))
    )
    (net (code "38") (name "Net-(J2-PadB5)") (class "Default")
      (node (ref "J2") (pin "B5") (pinfunction "B5_B5") (pintype "bidirectional"))
      (node (ref "R2-USB") (pin "1") (pinfunction "1_1") (pintype "passive"))
    )
    (net (code "39") (name "Net-(MCP73831-PROG)") (class "Default")
      (node (ref "MCP73831") (pin "5") (pinfunction "PROG_5") (pintype "input"))
      (node (ref "R2_BAT") (pin "1") (pinfunction "1_1") (pintype "passive"))
    )
    (net (code "40") (name "Net-(MCP73831-STAT)") (class "Default")
      (node (ref "MCP73831") (pin "1") (pinfunction "STAT_1") (pintype "output"))
      (node (ref "R1_BAT") (pin "1") (pinfunction "1_1") (pintype "passive"))
    )
    (net (code "41") (name "PREVGH") (class "Default")
      (node (ref "D5") (pin "1") (pinfunction "K_1") (pintype "bidirectional"))
      (node (ref "EPD_C9") (pin "1") (pinfunction "1_1") (pintype "passive"))
      (node (ref "J1") (pin "21") (pinfunction "21_21") (pintype "bidirectional"))
    )
    (net (code "42") (name "PREVGL") (class "Default")
      (node (ref "D4") (pin "2") (pinfunction "A_2") (pintype "bidirectional"))
      (node (ref "EPD_C11") (pin "1") (pinfunction "1_1") (pintype "passive"))
      (node (ref "J1") (pin "23") (pinfunction "23_23") (pintype "bidirectional"))
    )
    (net (code "43") (name "RESE") (class "Default")
      (node (ref "J1") (pin "3") (pinfunction "3_3") (pintype "bidirectional"))
      (node (ref "Q3") (pin "2") (pinfunction "S_2") (pintype "bidirectional"))
      (node (ref "R3") (pin "2") (pinfunction "2_2") (pintype "passive"))
    )
    (net (code "44") (name "RESE'") (class "Default")
      (node (ref "R2") (pin "2") (pinfunction "2_2") (pintype "passive"))
      (node (ref "R3") (pin "1") (pinfunction "1_1") (pintype "passive"))
      (node (ref "SJ1") (pin "2") (pinfunction "2_2") (pintype "passive"))
    )
    (net (code "45") (name "RESET") (class "Default")
      (node (ref "IC1") (pin "1") (pinfunction "VOUT_1") (pintype "bidirectional"))
      (node (ref "RESET_BUTTON") (pin "4") (pinfunction "4_4") (pintype "passive"))
      (node (ref "R_RESET") (pin "2") (pinfunction "2_2") (pintype "passive"))
      (node (ref "U2") (pin "3") (pinfunction "EN_3") (pintype "input"))
    )
    (net (code "46") (name "RTC_RST") (class "Default")
      (node (ref "U2") (pin "16") (pinfunction "IO18_16") (pintype "bidirectional"))
      (node (ref "U3") (pin "4") (pinfunction "~{RST}_4") (pintype "input"))
    )
    (net (code "47") (name "RX") (class "Default")
      (node (ref "TP2") (pin "TP") (pinfunction "TP_TP") (pintype "input"))
      (node (ref "U2") (pin "24") (pinfunction "RXD0/GPIO17_24") (pintype "bidirectional"))
    )
    (net (code "48") (name "SCK") (class "Default")
      (node (ref "D10") (pin "2") (pinfunction "2_2") (pintype "passive"))
      (node (ref "J1") (pin "13") (pinfunction "13_13") (pintype "bidirectional"))
      (node (ref "J4") (pin "P5") (pinfunction "CLK_P5") (pintype "bidirectional"))
      (node (ref "R6") (pin "1") (pinfunction "1_1") (pintype "passive"))
      (node (ref "TP8") (pin "TP") (pinfunction "TP_TP") (pintype "input"))
      (node (ref "U1") (pin "6") (pinfunction "CLK_6") (pintype "input"))
      (node (ref "U2") (pin "6") (pinfunction "IO6_6") (pintype "bidirectional"))
    )
    (net (code "49") (name "SCL") (class "Default")
      (node (ref "J3") (pin "1") (pinfunction "1_1") (pintype "power_in"))
      (node (ref "R2-PINH") (pin "1") (pinfunction "1_1") (pintype "passive"))
      (node (ref "SENSOR2") (pin "4") (pinfunction "SCK_4") (pintype "input"))
      (node (ref "U2") (pin "20") (pinfunction "IO22_20") (pintype "bidirectional"))
      (node (ref "U3") (pin "16") (pinfunction "SCL_16") (pintype "input"))
      (node (ref "U4") (pin "7") (pinfunction "SCL_7") (pintype "input"))
    )
    (net (code "50") (name "SDA") (class "Default")
      (node (ref "J3") (pin "2") (pinfunction "2_2") (pintype "power_in"))
      (node (ref "R1_PINH") (pin "1") (pinfunction "1_1") (pintype "passive"))
      (node (ref "SENSOR2") (pin "3") (pinfunction "SDI_3") (pintype "bidirectional"))
      (node (ref "U2") (pin "19") (pinfunction "IO21_19") (pintype "bidirectional"))
      (node (ref "U3") (pin "15") (pinfunction "SDA_15") (pintype "bidirectional"))
      (node (ref "U4") (pin "8") (pinfunction "SDA_8") (pintype "bidirectional"))
    )
    (net (code "51") (name "SRC") (class "Default")
      (node (ref "C4") (pin "2") (pinfunction "2_2") (pintype "passive"))
      (node (ref "D5") (pin "2") (pinfunction "A_2") (pintype "bidirectional"))
      (node (ref "L1") (pin "1") (pinfunction "1_1") (pintype "passive"))
      (node (ref "Q3") (pin "3") (pinfunction "D_3") (pintype "bidirectional"))
    )
    (net (code "52") (name "SS_SD") (class "Default")
      (node (ref "D8") (pin "2") (pinfunction "2_2") (pintype "passive"))
      (node (ref "J4") (pin "P2") (pinfunction "CD/DAT3_P2") (pintype "bidirectional"))
      (node (ref "R10") (pin "1") (pinfunction "1_1") (pintype "passive"))
      (node (ref "U2") (pin "4") (pinfunction "IO4_4") (pintype "bidirectional"))
    )
    (net (code "53") (name "TX") (class "Default")
      (node (ref "TP1") (pin "TP") (pinfunction "TP_TP") (pintype "input"))
      (node (ref "U2") (pin "25") (pinfunction "TXD0/GPIO16_25") (pintype "bidirectional"))
    )
    (net (code "54") (name "USB_D+") (class "Default")
      (node (ref "D1") (pin "1") (pinfunction "I/O1_1_1") (pintype "bidirectional"))
      (node (ref "U2") (pin "14") (pinfunction "IO13_14") (pintype "bidirectional"))
    )
    (net (code "55") (name "USB_D-") (class "Default")
      (node (ref "D1") (pin "3") (pinfunction "I/O2_1_3") (pintype "bidirectional"))
      (node (ref "U2") (pin "13") (pinfunction "IO12_13") (pintype "bidirectional"))
    )
    (net (code "56") (name "VBAT") (class "Default")
      (node (ref "C2_BAT") (pin "1") (pinfunction "1_1") (pintype "passive"))
      (node (ref "MCP73831") (pin "3") (pinfunction "VBAT_3") (pintype "power_in"))
      (node (ref "Q1") (pin "3") (pinfunction "D_3") (pintype "bidirectional"))
      (node (ref "TP3") (pin "TP") (pinfunction "TP_TP") (pintype "input"))
      (node (ref "U4") (pin "2") (pinfunction "CELL_2") (pintype "power_in"))
      (node (ref "U4") (pin "3") (pinfunction "VDD_3") (pintype "power_in"))
    )
    (net (code "57") (name "VBUS") (class "Default")
      (node (ref "C1_BAT") (pin "1") (pinfunction "1_1") (pintype "passive"))
      (node (ref "C4_USB") (pin "1") (pinfunction "1_1") (pintype "passive"))
      (node (ref "C5_USB") (pin "1") (pinfunction "1_1") (pintype "passive"))
      (node (ref "CHG_LED") (pin "A") (pinfunction "A_A") (pintype "passive"))
      (node (ref "D1") (pin "5") (pinfunction "VBUS_5") (pintype "bidirectional"))
      (node (ref "D2") (pin "2") (pinfunction "ANODE_2") (pintype "bidirectional"))
      (node (ref "MCP73831") (pin "4") (pinfunction "VIN_4") (pintype "power_in"))
      (node (ref "PFMF.050.1") (pin "2") (pinfunction "2_2") (pintype "passive"))
      (node (ref "Q1") (pin "1") (pinfunction "G_1") (pintype "bidirectional"))
      (node (ref "R1_PWRUSB") (pin "2") (pinfunction "2_2") (pintype "passive"))
      (node (ref "TP14") (pin "TP") (pinfunction "TP_TP") (pintype "input"))
    )
    (net (code "58") (name "VRTC") (class "Default")
      (node (ref "C10_SUPERCAP") (pin "2") (pinfunction "2_2") (pintype "passive"))
      (node (ref "C8") (pin "1") (pinfunction "1_1") (pintype "passive"))
      (node (ref "R_CAPACITOR") (pin "1") (pinfunction "1_1") (pintype "passive"))
      (node (ref "U3") (pin "14") (pinfunction "VBAT_14") (pintype "power_in"))
    )
    (net (code "59") (name "VUSB") (class "Default")
      (node (ref "J2") (pin "A4") (pinfunction "A4_A4") (pintype "bidirectional"))
      (node (ref "J2") (pin "A9") (pinfunction "A9_A9") (pintype "bidirectional"))
      (node (ref "J2") (pin "B4") (pinfunction "B4_B4") (pintype "bidirectional"))
      (node (ref "J2") (pin "B9") (pinfunction "B9_B9") (pintype "bidirectional"))
      (node (ref "PFMF.050.1") (pin "1") (pinfunction "1_1") (pintype "passive"))
    )
    (net (code "60") (name "unconnected-(BOOT_BUTTON-Pad1)") (class "Default")
      (node (ref "BOOT_BUTTON") (pin "1") (pinfunction "1_1") (pintype "passive"))
    )
    (net (code "61") (name "unconnected-(CHANGE_BUTTON-Pad1)") (class "Default")
      (node (ref "CHANGE_BUTTON") (pin "1") (pinfunction "1_1") (pintype "passive"))
    )
    (net (code "62") (name "unconnected-(IC1-NC-Pad4)") (class "Default")
      (node (ref "IC1") (pin "4") (pinfunction "NC_4") (pintype "no_connect"))
    )
    (net (code "63") (name "unconnected-(IC4-NC-Pad4)") (class "Default")
      (node (ref "IC4") (pin "4") (pinfunction "NC_4") (pintype "no_connect"))
    )
    (net (code "64") (name "unconnected-(J1-Pad1)") (class "Default")
      (node (ref "J1") (pin "1") (pinfunction "1_1") (pintype "bidirectional"))
    )
    (net (code "65") (name "unconnected-(J1-Pad7)") (class "Default")
      (node (ref "J1") (pin "7") (pinfunction "7_7") (pintype "bidirectional"))
    )
    (net (code "66") (name "unconnected-(J2-PadA8)") (class "Default")
      (node (ref "J2") (pin "A8") (pinfunction "A8_A8") (pintype "bidirectional"))
    )
    (net (code "67") (name "unconnected-(J2-PadB8)") (class "Default")
      (node (ref "J2") (pin "B8") (pinfunction "B8_B8") (pintype "bidirectional"))
    )
    (net (code "68") (name "unconnected-(J4-DAT1-PadP8)") (class "Default")
      (node (ref "J4") (pin "P8") (pinfunction "DAT1_P8") (pintype "bidirectional"))
    )
    (net (code "69") (name "unconnected-(J4-DAT2-PadP1)") (class "Default")
      (node (ref "J4") (pin "P1") (pinfunction "DAT2_P1") (pintype "bidirectional"))
    )
    (net (code "70") (name "unconnected-(J4-DETECTION_1-PadS1)") (class "Default")
      (node (ref "J4") (pin "S1") (pinfunction "DETECTION_1_S1") (pintype "bidirectional"))
    )
    (net (code "71") (name "unconnected-(J4-DETECTION_2-PadS2)") (class "Default")
      (node (ref "J4") (pin "S2") (pinfunction "DETECTION_2_S2") (pintype "bidirectional"))
    )
    (net (code "72") (name "unconnected-(J4-VSS-PadP6)") (class "Default")
      (node (ref "J4") (pin "P6") (pinfunction "VSS_P6") (pintype "bidirectional"))
    )
    (net (code "73") (name "unconnected-(U2-NC-Pad22)") (class "Default")
      (node (ref "U2") (pin "22") (pinfunction "NC_22") (pintype "no_connect"))
    )
    (net (code "74") (name "unconnected-(U4-~{ALERT}-Pad5)") (class "Default")
      (node (ref "U4") (pin "5") (pinfunction "~{ALERT}_5") (pintype "output"))
    )
  )
)
